# firefly.net
KiCad netlist of a schematic drawn in EAGLE
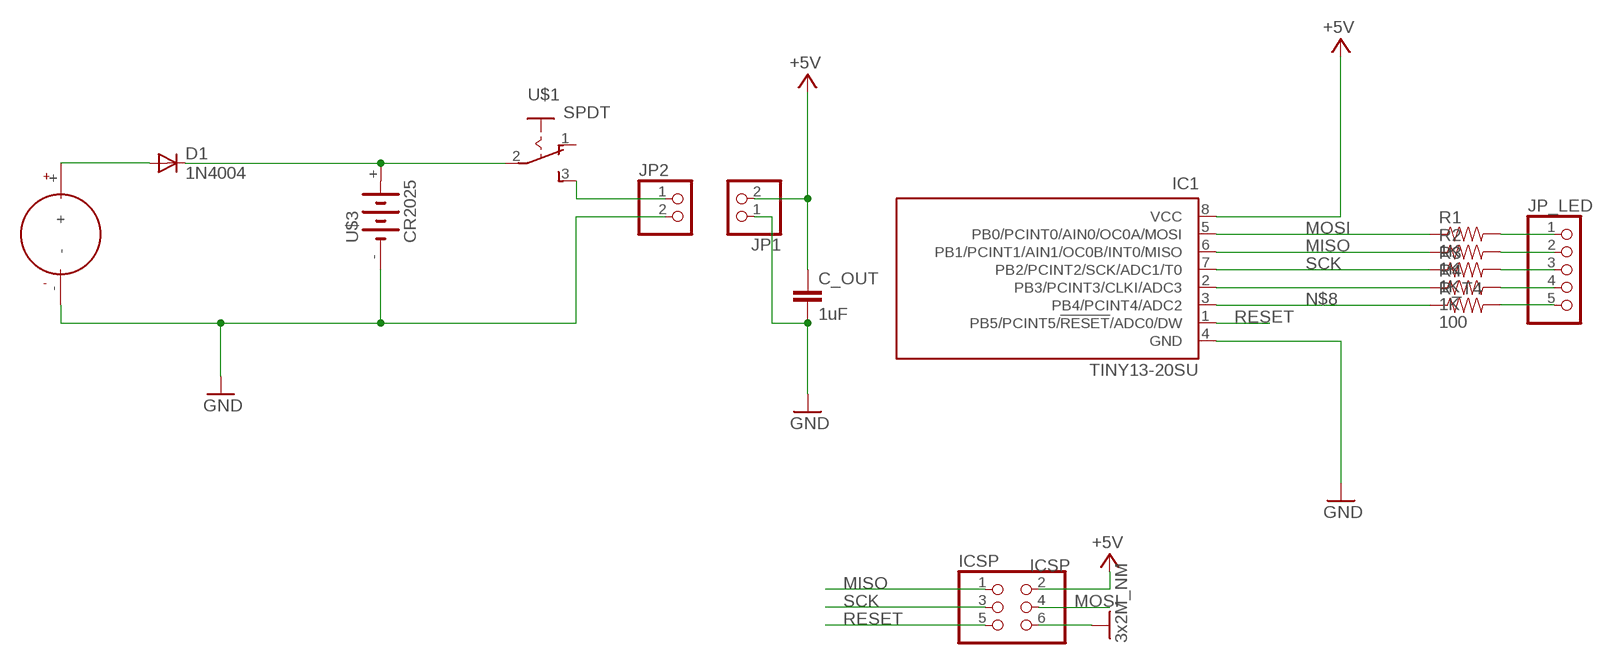
[diagram p0: schematic, sheet 1]

(export (version "E")
  (design (tool "Eeschema 10.0.6"))
  (components
    (comp (ref "C_OUT")
      (value "1uF")
      (footprint "eagle-import:0805")
      (libsource (lib "eagle-import") (part "CAP0805"))
    )
    (comp (ref "D1")
      (value "1N4004")
      (footprint "eagle-import:DO41-10")
      (libsource (lib "eagle-import") (part "1N4004"))
    )
    (comp (ref "IC1")
      (value "TINY13-20SU")
      (footprint "eagle-import:8S2")
      (fields (field (name "MPN") "ATTINY13-20SU"))
      (libsource (lib "eagle-import") (part "TINY13SU-20"))
    )
    (comp (ref "ICSP")
      (value "ICSP")
      (footprint "eagle-import:2X03")
      (libsource (lib "eagle-import") (part "PINHD-2X3"))
    )
    (comp (ref "JP1")
      (value "PINHD-1X2")
      (footprint "eagle-import:1X02")
      (libsource (lib "eagle-import") (part "PINHD-1X2"))
    )
    (comp (ref "JP2")
      (value "PINHD-1X2")
      (footprint "eagle-import:1X02")
      (libsource (lib "eagle-import") (part "PINHD-1X2"))
    )
    (comp (ref "JP_LED")
      (value "PINHD-1X5")
      (footprint "eagle-import:1X05")
      (libsource (lib "eagle-import") (part "PINHD-1X5"))
    )
    (comp (ref "R1")
      (value "1K")
      (footprint "eagle-import:0805")
      (libsource (lib "eagle-import") (part "RESISTOR"))
    )
    (comp (ref "R2")
      (value "1K")
      (footprint "eagle-import:0805")
      (libsource (lib "eagle-import") (part "RESISTOR"))
    )
    (comp (ref "R3")
      (value "1K")
      (footprint "eagle-import:0805")
      (libsource (lib "eagle-import") (part "RESISTOR"))
    )
    (comp (ref "R4")
      (value "1K")
      (footprint "eagle-import:0805")
      (libsource (lib "eagle-import") (part "RESISTOR"))
    )
    (comp (ref "R_T4")
      (value "100")
      (footprint "eagle-import:0805")
      (libsource (lib "eagle-import") (part "RESISTOR"))
    )
    (comp (ref "U$1")
      (value "SPDT")
      (footprint "eagle-import:SPDT")
      (libsource (lib "eagle-import") (part "SPDT"))
    )
    (comp (ref "U$3")
      (value "CR2025")
      (footprint "eagle-import:CR2025")
      (libsource (lib "eagle-import") (part "CR2025"))
    )
    (comp (ref "U$4")
      (value "PANEL_60_60")
      (footprint "eagle-import:PANEL_60_60")
      (libsource (lib "eagle-import") (part "PANEL_60_60"))
    )
  )
  (nets
    (net (code "1") (name "+5V") (class "Default")
      (node (ref "C_OUT") (pin "1") (pinfunction "1_1") (pintype "passive"))
      (node (ref "IC1") (pin "8") (pinfunction "VCC_8") (pintype "power_in"))
      (node (ref "ICSP") (pin "2") (pinfunction "2_2") (pintype "passive"))
      (node (ref "JP1") (pin "2") (pinfunction "2_2") (pintype "passive"))
    )
    (net (code "2") (name "/MISO") (class "Default")
      (node (ref "IC1") (pin "6") (pinfunction "PB1/PCINT1/AIN1/OC0B/INT0/MISO_6") (pintype "bidirectional"))
      (node (ref "ICSP") (pin "1") (pinfunction "1_1") (pintype "passive"))
      (node (ref "R2") (pin "1") (pinfunction "1_1") (pintype "passive"))
    )
    (net (code "3") (name "/MOSI") (class "Default")
      (node (ref "IC1") (pin "5") (pinfunction "PB0/PCINT0/AIN0/OC0A/MOSI_5") (pintype "bidirectional"))
      (node (ref "ICSP") (pin "4") (pinfunction "4_4") (pintype "passive"))
      (node (ref "R1") (pin "1") (pinfunction "1_1") (pintype "passive"))
    )
    (net (code "4") (name "/N$8") (class "Default")
      (node (ref "IC1") (pin "3") (pinfunction "PB4/PCINT4/ADC2_3") (pintype "bidirectional"))
      (node (ref "R_T4") (pin "1") (pinfunction "1_1") (pintype "passive"))
    )
    (net (code "5") (name "/RESET") (class "Default")
      (node (ref "IC1") (pin "1") (pinfunction "PB5/PCINT5/~{RESET}/ADC0/DW_1") (pintype "bidirectional"))
      (node (ref "ICSP") (pin "5") (pinfunction "5_5") (pintype "passive"))
    )
    (net (code "6") (name "/SCK") (class "Default")
      (node (ref "IC1") (pin "7") (pinfunction "PB2/PCINT2/SCK/ADC1/T0_7") (pintype "bidirectional"))
      (node (ref "ICSP") (pin "3") (pinfunction "3_3") (pintype "passive"))
      (node (ref "R3") (pin "1") (pinfunction "1_1") (pintype "passive"))
    )
    (net (code "7") (name "3x2M_NM") (class "Default")
      (node (ref "C_OUT") (pin "2") (pinfunction "2_2") (pintype "passive"))
      (node (ref "IC1") (pin "4") (pinfunction "GND_4") (pintype "power_in"))
      (node (ref "ICSP") (pin "6") (pinfunction "6_6") (pintype "passive"))
      (node (ref "JP1") (pin "1") (pinfunction "1_1") (pintype "passive"))
      (node (ref "JP2") (pin "2") (pinfunction "2_2") (pintype "passive"))
      (node (ref "U$3") (pin "-") (pinfunction "-_-") (pintype "passive"))
      (node (ref "U$4") (pin "-") (pinfunction "-_-") (pintype "bidirectional"))
    )
    (net (code "8") (name "Net-(D1-PadA)") (class "Default")
      (node (ref "D1") (pin "A") (pinfunction "A_A") (pintype "passive"))
      (node (ref "U$4") (pin "+") (pinfunction "+_+") (pintype "bidirectional"))
    )
    (net (code "9") (name "Net-(IC1-PB3{slash}PCINT3{slash}CLKI{slash}ADC3)") (class "Default")
      (node (ref "IC1") (pin "2") (pinfunction "PB3/PCINT3/CLKI/ADC3_2") (pintype "bidirectional"))
      (node (ref "R4") (pin "1") (pinfunction "1_1") (pintype "passive"))
    )
    (net (code "10") (name "Net-(JP_LED-Pad1)") (class "Default")
      (node (ref "JP_LED") (pin "1") (pinfunction "1_1") (pintype "passive"))
      (node (ref "R1") (pin "2") (pinfunction "2_2") (pintype "passive"))
    )
    (net (code "11") (name "Net-(JP_LED-Pad2)") (class "Default")
      (node (ref "JP_LED") (pin "2") (pinfunction "2_2") (pintype "passive"))
      (node (ref "R2") (pin "2") (pinfunction "2_2") (pintype "passive"))
    )
    (net (code "12") (name "Net-(JP_LED-Pad3)") (class "Default")
      (node (ref "JP_LED") (pin "3") (pinfunction "3_3") (pintype "passive"))
      (node (ref "R3") (pin "2") (pinfunction "2_2") (pintype "passive"))
    )
    (net (code "13") (name "Net-(JP_LED-Pad4)") (class "Default")
      (node (ref "JP_LED") (pin "4") (pinfunction "4_4") (pintype "passive"))
      (node (ref "R4") (pin "2") (pinfunction "2_2") (pintype "passive"))
    )
    (net (code "14") (name "Net-(JP_LED-Pad5)") (class "Default")
      (node (ref "JP_LED") (pin "5") (pinfunction "5_5") (pintype "passive"))
      (node (ref "R_T4") (pin "2") (pinfunction "2_2") (pintype "passive"))
    )
    (net (code "15") (name "Net-(U$1-P)") (class "Default")
      (node (ref "D1") (pin "C") (pinfunction "C_C") (pintype "passive"))
      (node (ref "U$1") (pin "2") (pinfunction "P_2") (pintype "passive"))
      (node (ref "U$3") (pin "+") (pinfunction "+_+") (pintype "passive"))
    )
    (net (code "16") (name "Net-(U$1-S)") (class "Default")
      (node (ref "JP2") (pin "1") (pinfunction "1_1") (pintype "passive"))
      (node (ref "U$1") (pin "3") (pinfunction "S_3") (pintype "passive"))
    )
    (net (code "17") (name "unconnected-(U$1-O-Pad1)") (class "Default")
      (node (ref "U$1") (pin "1") (pinfunction "O_1") (pintype "passive"))
    )
  )
)
